# TC_TFT.net
KiCad netlist of a schematic drawn in EAGLE
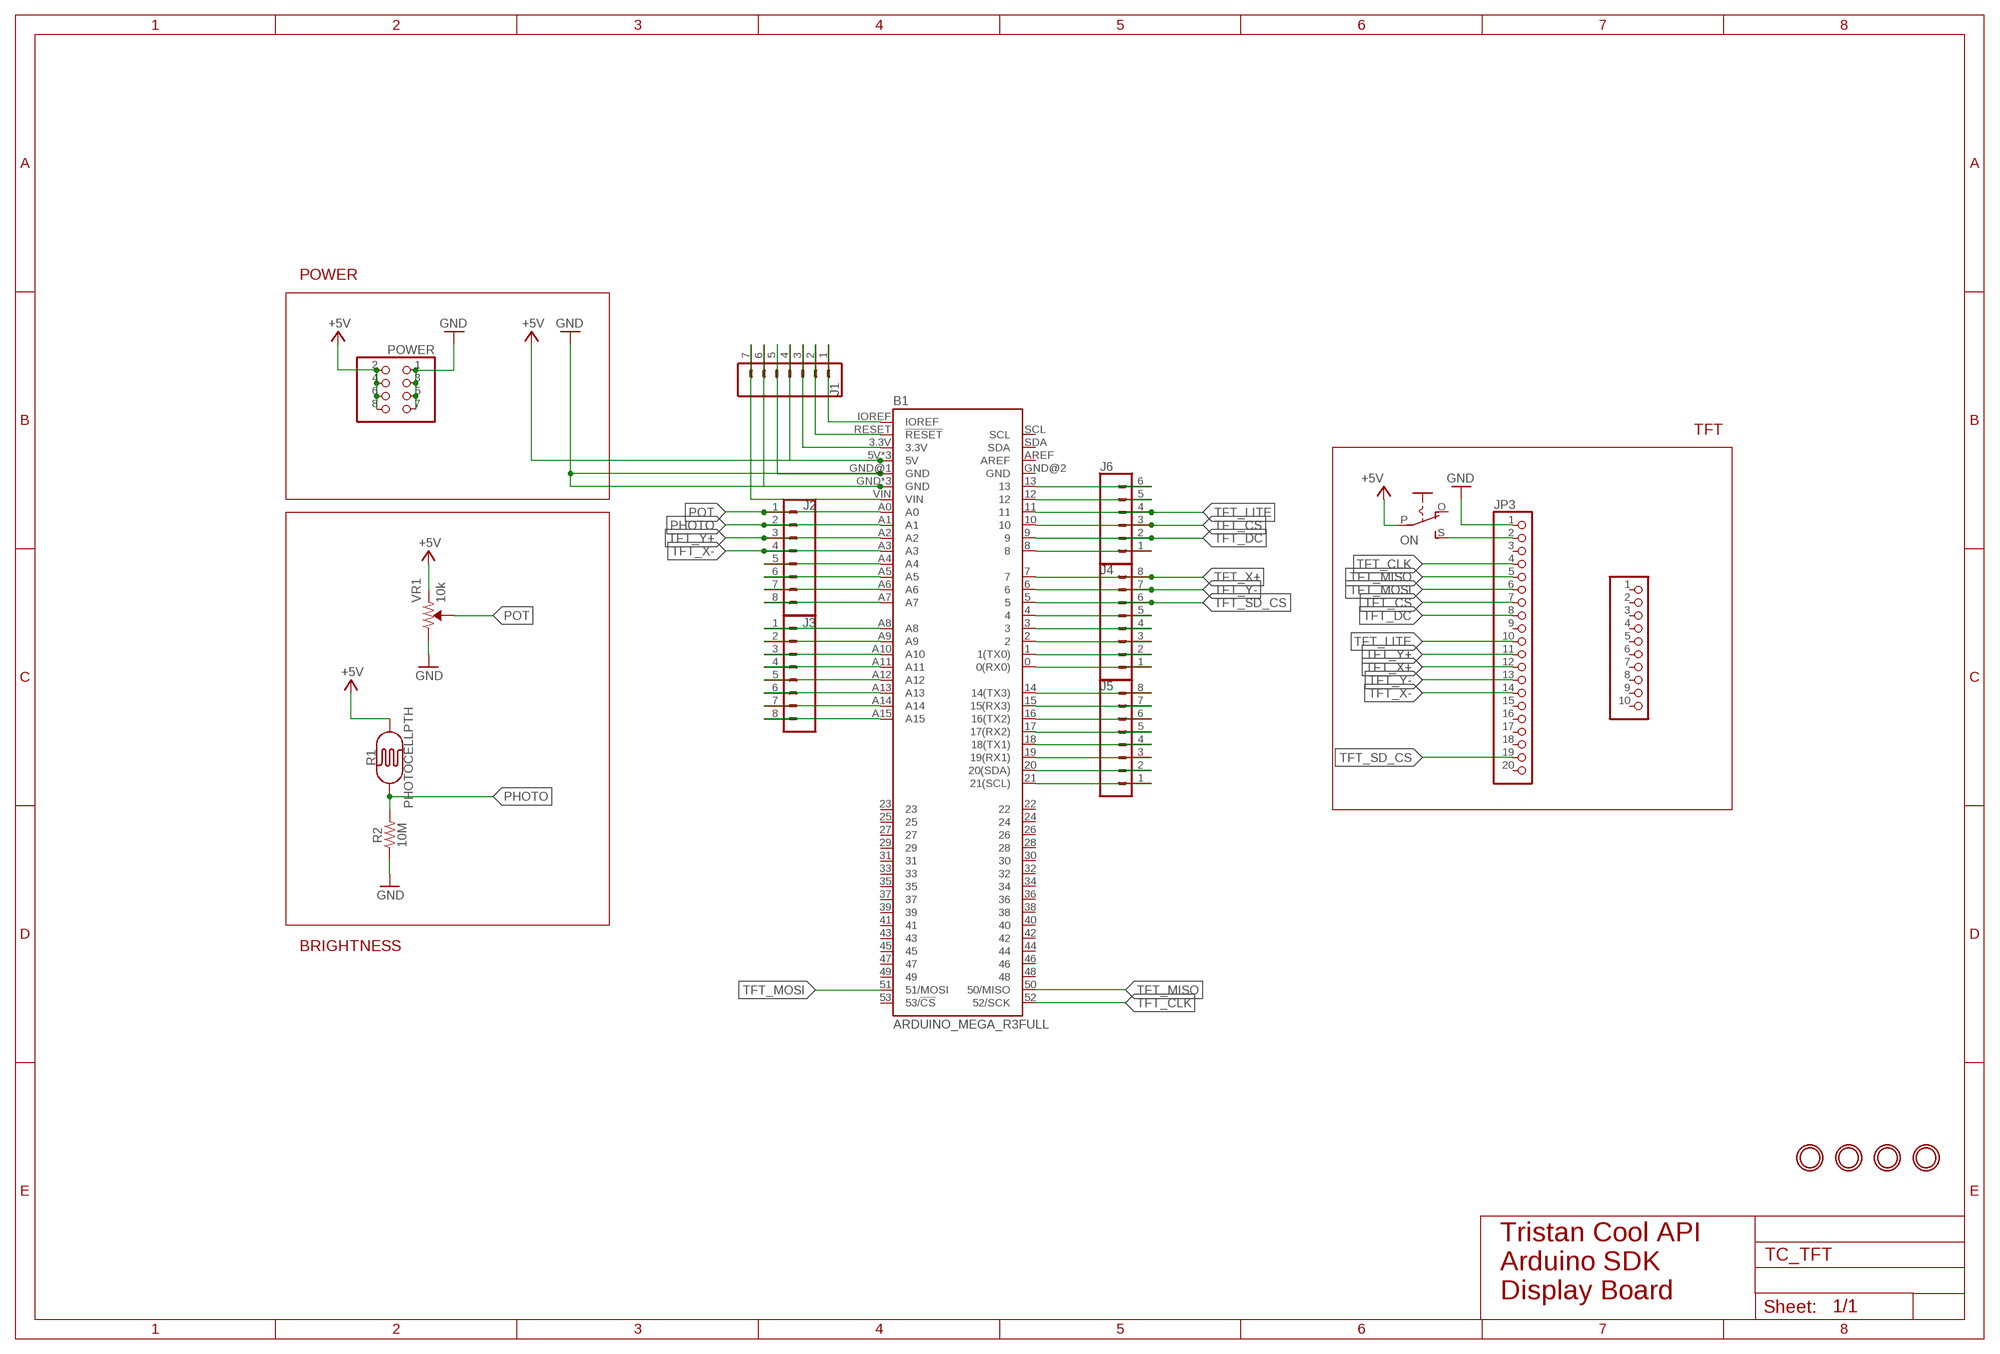
[diagram p0: schematic, sheet 1]

(export (version "E")
  (design (tool "Eeschema 10.0.6"))
  (components
    (comp (ref "B1")
      (value "ARDUINO_MEGA_R3FULL")
      (footprint "eagle-import:ARDUINO_MEGA_NO_SILK")
      (libsource (lib "eagle-import") (part "ARDUINO_MEGA_R3FULL"))
    )
    (comp (ref "J1")
      (value "CONN_07")
      (footprint "eagle-import:1X07")
      (libsource (lib "eagle-import") (part "CONN_07"))
    )
    (comp (ref "J2")
      (value "CONN_08\"")
      (footprint "eagle-import:1X08")
      (libsource (lib "eagle-import") (part "CONN_08{dblquote}"))
    )
    (comp (ref "J3")
      (value "CONN_08\"")
      (footprint "eagle-import:1X08")
      (libsource (lib "eagle-import") (part "CONN_08{dblquote}"))
    )
    (comp (ref "J4")
      (value "CONN_08\"")
      (footprint "eagle-import:1X08")
      (libsource (lib "eagle-import") (part "CONN_08{dblquote}"))
    )
    (comp (ref "J5")
      (value "CONN_08\"")
      (footprint "eagle-import:1X08")
      (libsource (lib "eagle-import") (part "CONN_08{dblquote}"))
    )
    (comp (ref "J6")
      (value "CONN_06SILK_FEMALE_PTH")
      (footprint "eagle-import:1X06")
      (libsource (lib "eagle-import") (part "CONN_06SILK_FEMALE_PTH"))
    )
    (comp (ref "JP3")
      (value "HEADER-1X20ROUND")
      (footprint "eagle-import:1X20_ROUND")
      (libsource (lib "eagle-import") (part "HEADER-1X20ROUND"))
    )
    (comp (ref "ON")
      (value "EG1218S")
      (footprint "eagle-import:EG1218")
      (libsource (lib "eagle-import") (part "EG1218S"))
    )
    (comp (ref "POWER")
      (value "PINHD-2X4")
      (footprint "eagle-import:2X04")
      (libsource (lib "eagle-import") (part "PINHD-2X4"))
    )
    (comp (ref "R1")
      (value "PHOTOCELLPTH")
      (footprint "eagle-import:PHOTOCELL")
      (libsource (lib "eagle-import") (part "PHOTOCELLPTH"))
    )
    (comp (ref "R2")
      (value "10M")
      (footprint "eagle-import:0603")
      (libsource (lib "eagle-import") (part "10MOHM-0603-1/10W-5%"))
    )
    (comp (ref "U$1")
      (value "MOUNTINGHOLE3.0THIN")
      (footprint "eagle-import:MOUNTINGHOLE_3.0_PLATEDTHIN")
      (libsource (lib "eagle-import") (part "MOUNTINGHOLE3.0THIN"))
    )
    (comp (ref "U$2")
      (value "MOUNTINGHOLE3.0THIN")
      (footprint "eagle-import:MOUNTINGHOLE_3.0_PLATEDTHIN")
      (libsource (lib "eagle-import") (part "MOUNTINGHOLE3.0THIN"))
    )
    (comp (ref "U$3")
      (value "MOUNTINGHOLE3.0THIN")
      (footprint "eagle-import:MOUNTINGHOLE_3.0_PLATEDTHIN")
      (libsource (lib "eagle-import") (part "MOUNTINGHOLE3.0THIN"))
    )
    (comp (ref "U$4")
      (value "MOUNTINGHOLE3.0THIN")
      (footprint "eagle-import:MOUNTINGHOLE_3.0_PLATEDTHIN")
      (libsource (lib "eagle-import") (part "MOUNTINGHOLE3.0THIN"))
    )
    (comp (ref "U$5")
      (value "PINHD-1X10")
      (footprint "eagle-import:1X10-BIG")
      (libsource (lib "eagle-import") (part "PINHD-1X10"))
    )
    (comp (ref "VR1")
      (value "10k")
      (footprint "eagle-import:TRIMPOT-PTH-3386U")
      (libsource (lib "eagle-import") (part "TRIMPOT-PTH-10MM-KNOB-1/2W-10%"))
    )
  )
  (nets
    (net (code "1") (name "+5V") (class "Default")
      (node (ref "B1") (pin "5V") (pinfunction "5V_5V") (pintype "bidirectional"))
      (node (ref "B1") (pin "5V@1") (pinfunction "5V_5V@1") (pintype "bidirectional"))
      (node (ref "B1") (pin "5V@2") (pinfunction "5V_5V@2") (pintype "bidirectional"))
      (node (ref "J1") (pin "4") (pinfunction "4_4") (pintype "passive"))
      (node (ref "ON") (pin "P") (pinfunction "P_P") (pintype "passive"))
      (node (ref "POWER") (pin "2") (pinfunction "2_2") (pintype "passive"))
      (node (ref "POWER") (pin "4") (pinfunction "4_4") (pintype "passive"))
      (node (ref "POWER") (pin "6") (pinfunction "6_6") (pintype "passive"))
      (node (ref "POWER") (pin "8") (pinfunction "8_8") (pintype "passive"))
      (node (ref "R1") (pin "2") (pinfunction "P$2_2") (pintype "bidirectional"))
      (node (ref "VR1") (pin "1") (pinfunction "CCW_1") (pintype "passive"))
    )
    (net (code "2") (name "GND") (class "Default")
      (node (ref "B1") (pin "GND") (pinfunction "GND_GND") (pintype "bidirectional"))
      (node (ref "B1") (pin "GND@1") (pinfunction "GND_GND@1") (pintype "bidirectional"))
      (node (ref "B1") (pin "GND@3") (pinfunction "GND_GND@3") (pintype "bidirectional"))
      (node (ref "B1") (pin "GND@4") (pinfunction "GND_GND@4") (pintype "bidirectional"))
      (node (ref "J1") (pin "5") (pinfunction "5_5") (pintype "passive"))
      (node (ref "J1") (pin "6") (pinfunction "6_6") (pintype "passive"))
      (node (ref "JP3") (pin "1") (pinfunction "1_1") (pintype "passive"))
      (node (ref "POWER") (pin "1") (pinfunction "1_1") (pintype "passive"))
      (node (ref "POWER") (pin "3") (pinfunction "3_3") (pintype "passive"))
      (node (ref "POWER") (pin "5") (pinfunction "5_5") (pintype "passive"))
      (node (ref "POWER") (pin "7") (pinfunction "7_7") (pintype "passive"))
      (node (ref "R2") (pin "1") (pinfunction "1_1") (pintype "passive"))
      (node (ref "VR1") (pin "3") (pinfunction "CW_3") (pintype "passive"))
    )
    (net (code "3") (name "Net-(B1-0(RX0))") (class "Default")
      (node (ref "B1") (pin "0") (pinfunction "0(RX0)_0") (pintype "bidirectional"))
      (node (ref "J4") (pin "1") (pinfunction "1_1") (pintype "passive"))
    )
    (net (code "4") (name "Net-(B1-1(TX0))") (class "Default")
      (node (ref "B1") (pin "1") (pinfunction "1(TX0)_1") (pintype "bidirectional"))
      (node (ref "J4") (pin "2") (pinfunction "2_2") (pintype "passive"))
    )
    (net (code "5") (name "Net-(B1-14(TX3))") (class "Default")
      (node (ref "B1") (pin "14") (pinfunction "14(TX3)_14") (pintype "bidirectional"))
      (node (ref "J5") (pin "8") (pinfunction "8_8") (pintype "passive"))
    )
    (net (code "6") (name "Net-(B1-15(RX3))") (class "Default")
      (node (ref "B1") (pin "15") (pinfunction "15(RX3)_15") (pintype "bidirectional"))
      (node (ref "J5") (pin "7") (pinfunction "7_7") (pintype "passive"))
    )
    (net (code "7") (name "Net-(B1-16(TX2))") (class "Default")
      (node (ref "B1") (pin "16") (pinfunction "16(TX2)_16") (pintype "bidirectional"))
      (node (ref "J5") (pin "6") (pinfunction "6_6") (pintype "passive"))
    )
    (net (code "8") (name "Net-(B1-17(RX2))") (class "Default")
      (node (ref "B1") (pin "17") (pinfunction "17(RX2)_17") (pintype "bidirectional"))
      (node (ref "J5") (pin "5") (pinfunction "5_5") (pintype "passive"))
    )
    (net (code "9") (name "Net-(B1-18(TX1))") (class "Default")
      (node (ref "B1") (pin "18") (pinfunction "18(TX1)_18") (pintype "bidirectional"))
      (node (ref "J5") (pin "4") (pinfunction "4_4") (pintype "passive"))
    )
    (net (code "10") (name "Net-(B1-19(RX1))") (class "Default")
      (node (ref "B1") (pin "19") (pinfunction "19(RX1)_19") (pintype "bidirectional"))
      (node (ref "J5") (pin "3") (pinfunction "3_3") (pintype "passive"))
    )
    (net (code "11") (name "Net-(B1-20(SDA))") (class "Default")
      (node (ref "B1") (pin "20") (pinfunction "20(SDA)_20") (pintype "bidirectional"))
      (node (ref "J5") (pin "2") (pinfunction "2_2") (pintype "passive"))
    )
    (net (code "12") (name "Net-(B1-21(SCL))") (class "Default")
      (node (ref "B1") (pin "21") (pinfunction "21(SCL)_21") (pintype "bidirectional"))
      (node (ref "J5") (pin "1") (pinfunction "1_1") (pintype "passive"))
    )
    (net (code "13") (name "Net-(B1-Pad2)") (class "Default")
      (node (ref "B1") (pin "2") (pinfunction "2_2") (pintype "bidirectional"))
      (node (ref "J4") (pin "3") (pinfunction "3_3") (pintype "passive"))
    )
    (net (code "14") (name "Net-(B1-Pad3)") (class "Default")
      (node (ref "B1") (pin "3") (pinfunction "3_3") (pintype "bidirectional"))
      (node (ref "J4") (pin "4") (pinfunction "4_4") (pintype "passive"))
    )
    (net (code "15") (name "Net-(B1-Pad3.3V)") (class "Default")
      (node (ref "B1") (pin "3.3V") (pinfunction "3.3V_3.3V") (pintype "bidirectional"))
      (node (ref "J1") (pin "3") (pinfunction "3_3") (pintype "passive"))
    )
    (net (code "16") (name "Net-(B1-Pad4)") (class "Default")
      (node (ref "B1") (pin "4") (pinfunction "4_4") (pintype "bidirectional"))
      (node (ref "J4") (pin "5") (pinfunction "5_5") (pintype "passive"))
    )
    (net (code "17") (name "Net-(B1-Pad8)") (class "Default")
      (node (ref "B1") (pin "8") (pinfunction "8_8") (pintype "bidirectional"))
      (node (ref "J6") (pin "1") (pinfunction "1_1") (pintype "passive"))
    )
    (net (code "18") (name "Net-(B1-Pad12)") (class "Default")
      (node (ref "B1") (pin "12") (pinfunction "12_12") (pintype "bidirectional"))
      (node (ref "J6") (pin "5") (pinfunction "5_5") (pintype "passive"))
    )
    (net (code "19") (name "Net-(B1-Pad13)") (class "Default")
      (node (ref "B1") (pin "13") (pinfunction "13_13") (pintype "bidirectional"))
      (node (ref "J6") (pin "6") (pinfunction "6_6") (pintype "passive"))
    )
    (net (code "20") (name "Net-(B1-PadA4)") (class "Default")
      (node (ref "B1") (pin "A4") (pinfunction "A4_A4") (pintype "bidirectional"))
      (node (ref "J2") (pin "5") (pinfunction "5_5") (pintype "passive"))
    )
    (net (code "21") (name "Net-(B1-PadA5)") (class "Default")
      (node (ref "B1") (pin "A5") (pinfunction "A5_A5") (pintype "bidirectional"))
      (node (ref "J2") (pin "6") (pinfunction "6_6") (pintype "passive"))
    )
    (net (code "22") (name "Net-(B1-PadA6)") (class "Default")
      (node (ref "B1") (pin "A6") (pinfunction "A6_A6") (pintype "bidirectional"))
      (node (ref "J2") (pin "7") (pinfunction "7_7") (pintype "passive"))
    )
    (net (code "23") (name "Net-(B1-PadA7)") (class "Default")
      (node (ref "B1") (pin "A7") (pinfunction "A7_A7") (pintype "bidirectional"))
      (node (ref "J2") (pin "8") (pinfunction "8_8") (pintype "passive"))
    )
    (net (code "24") (name "Net-(B1-PadA8)") (class "Default")
      (node (ref "B1") (pin "A8") (pinfunction "A8_A8") (pintype "bidirectional"))
      (node (ref "J3") (pin "1") (pinfunction "1_1") (pintype "passive"))
    )
    (net (code "25") (name "Net-(B1-PadA9)") (class "Default")
      (node (ref "B1") (pin "A9") (pinfunction "A9_A9") (pintype "bidirectional"))
      (node (ref "J3") (pin "2") (pinfunction "2_2") (pintype "passive"))
    )
    (net (code "26") (name "Net-(B1-PadA10)") (class "Default")
      (node (ref "B1") (pin "A10") (pinfunction "A10_A10") (pintype "bidirectional"))
      (node (ref "J3") (pin "3") (pinfunction "3_3") (pintype "passive"))
    )
    (net (code "27") (name "Net-(B1-PadA11)") (class "Default")
      (node (ref "B1") (pin "A11") (pinfunction "A11_A11") (pintype "bidirectional"))
      (node (ref "J3") (pin "4") (pinfunction "4_4") (pintype "passive"))
    )
    (net (code "28") (name "Net-(B1-PadA12)") (class "Default")
      (node (ref "B1") (pin "A12") (pinfunction "A12_A12") (pintype "bidirectional"))
      (node (ref "J3") (pin "5") (pinfunction "5_5") (pintype "passive"))
    )
    (net (code "29") (name "Net-(B1-PadA13)") (class "Default")
      (node (ref "B1") (pin "A13") (pinfunction "A13_A13") (pintype "bidirectional"))
      (node (ref "J3") (pin "6") (pinfunction "6_6") (pintype "passive"))
    )
    (net (code "30") (name "Net-(B1-PadA14)") (class "Default")
      (node (ref "B1") (pin "A14") (pinfunction "A14_A14") (pintype "bidirectional"))
      (node (ref "J3") (pin "7") (pinfunction "7_7") (pintype "passive"))
    )
    (net (code "31") (name "Net-(B1-PadA15)") (class "Default")
      (node (ref "B1") (pin "A15") (pinfunction "A15_A15") (pintype "bidirectional"))
      (node (ref "J3") (pin "8") (pinfunction "8_8") (pintype "passive"))
    )
    (net (code "32") (name "Net-(B1-PadIOREF)") (class "Default")
      (node (ref "B1") (pin "IOREF") (pinfunction "IOREF_IOREF") (pintype "bidirectional"))
      (node (ref "J1") (pin "1") (pinfunction "1_1") (pintype "passive"))
    )
    (net (code "33") (name "Net-(B1-PadVIN)") (class "Default")
      (node (ref "B1") (pin "VIN") (pinfunction "VIN_VIN") (pintype "bidirectional"))
      (node (ref "J1") (pin "7") (pinfunction "7_7") (pintype "passive"))
    )
    (net (code "34") (name "Net-(B1-~{RESET})") (class "Default")
      (node (ref "B1") (pin "RESET") (pinfunction "~{RESET}_RESET") (pintype "bidirectional"))
      (node (ref "J1") (pin "2") (pinfunction "2_2") (pintype "passive"))
    )
    (net (code "35") (name "Net-(JP3-Pad2)") (class "Default")
      (node (ref "JP3") (pin "2") (pinfunction "2_2") (pintype "passive"))
      (node (ref "ON") (pin "S") (pinfunction "S_S") (pintype "passive"))
    )
    (net (code "36") (name "PHOTO") (class "Default")
      (node (ref "B1") (pin "A1") (pinfunction "A1_A1") (pintype "bidirectional"))
      (node (ref "J2") (pin "2") (pinfunction "2_2") (pintype "passive"))
      (node (ref "R1") (pin "1") (pinfunction "P$1_1") (pintype "bidirectional"))
      (node (ref "R2") (pin "2") (pinfunction "2_2") (pintype "passive"))
    )
    (net (code "37") (name "POT") (class "Default")
      (node (ref "B1") (pin "A0") (pinfunction "A0_A0") (pintype "bidirectional"))
      (node (ref "J2") (pin "1") (pinfunction "1_1") (pintype "passive"))
      (node (ref "VR1") (pin "2") (pinfunction "WIPER_2") (pintype "passive"))
    )
    (net (code "38") (name "TFT_CLK") (class "Default")
      (node (ref "B1") (pin "52") (pinfunction "52/SCK_52") (pintype "bidirectional"))
      (node (ref "JP3") (pin "4") (pinfunction "4_4") (pintype "passive"))
    )
    (net (code "39") (name "TFT_CS") (class "Default")
      (node (ref "B1") (pin "10") (pinfunction "10_10") (pintype "bidirectional"))
      (node (ref "J6") (pin "3") (pinfunction "3_3") (pintype "passive"))
      (node (ref "JP3") (pin "7") (pinfunction "7_7") (pintype "passive"))
    )
    (net (code "40") (name "TFT_DC") (class "Default")
      (node (ref "B1") (pin "9") (pinfunction "9_9") (pintype "bidirectional"))
      (node (ref "J6") (pin "2") (pinfunction "2_2") (pintype "passive"))
      (node (ref "JP3") (pin "8") (pinfunction "8_8") (pintype "passive"))
    )
    (net (code "41") (name "TFT_LITE") (class "Default")
      (node (ref "B1") (pin "11") (pinfunction "11_11") (pintype "bidirectional"))
      (node (ref "J6") (pin "4") (pinfunction "4_4") (pintype "passive"))
      (node (ref "JP3") (pin "10") (pinfunction "10_10") (pintype "passive"))
    )
    (net (code "42") (name "TFT_MISO") (class "Default")
      (node (ref "B1") (pin "50") (pinfunction "50/MISO_50") (pintype "bidirectional"))
      (node (ref "JP3") (pin "5") (pinfunction "5_5") (pintype "passive"))
    )
    (net (code "43") (name "TFT_MOSI") (class "Default")
      (node (ref "B1") (pin "51") (pinfunction "51/MOSI_51") (pintype "bidirectional"))
      (node (ref "JP3") (pin "6") (pinfunction "6_6") (pintype "passive"))
    )
    (net (code "44") (name "TFT_SD_CS") (class "Default")
      (node (ref "B1") (pin "5") (pinfunction "5_5") (pintype "bidirectional"))
      (node (ref "J4") (pin "6") (pinfunction "6_6") (pintype "passive"))
      (node (ref "JP3") (pin "19") (pinfunction "19_19") (pintype "passive"))
    )
    (net (code "45") (name "TFT_X+") (class "Default")
      (node (ref "B1") (pin "7") (pinfunction "7_7") (pintype "bidirectional"))
      (node (ref "J4") (pin "8") (pinfunction "8_8") (pintype "passive"))
      (node (ref "JP3") (pin "12") (pinfunction "12_12") (pintype "passive"))
    )
    (net (code "46") (name "TFT_X-") (class "Default")
      (node (ref "B1") (pin "A3") (pinfunction "A3_A3") (pintype "bidirectional"))
      (node (ref "J2") (pin "4") (pinfunction "4_4") (pintype "passive"))
      (node (ref "JP3") (pin "14") (pinfunction "14_14") (pintype "passive"))
    )
    (net (code "47") (name "TFT_Y+") (class "Default")
      (node (ref "B1") (pin "A2") (pinfunction "A2_A2") (pintype "bidirectional"))
      (node (ref "J2") (pin "3") (pinfunction "3_3") (pintype "passive"))
      (node (ref "JP3") (pin "11") (pinfunction "11_11") (pintype "passive"))
    )
    (net (code "48") (name "TFT_Y-") (class "Default")
      (node (ref "B1") (pin "6") (pinfunction "6_6") (pintype "bidirectional"))
      (node (ref "J4") (pin "7") (pinfunction "7_7") (pintype "passive"))
      (node (ref "JP3") (pin "13") (pinfunction "13_13") (pintype "passive"))
    )
    (net (code "49") (name "unconnected-(B1-53{slash}~{CS}-Pad53)") (class "Default")
      (node (ref "B1") (pin "53") (pinfunction "53/~{CS}_53") (pintype "bidirectional"))
    )
    (net (code "50") (name "unconnected-(B1-GND-PadGND@2)") (class "Default")
      (node (ref "B1") (pin "GND@2") (pinfunction "GND_GND@2") (pintype "bidirectional"))
    )
    (net (code "51") (name "unconnected-(B1-Pad22)") (class "Default")
      (node (ref "B1") (pin "22") (pinfunction "22_22") (pintype "bidirectional"))
    )
    (net (code "52") (name "unconnected-(B1-Pad23)") (class "Default")
      (node (ref "B1") (pin "23") (pinfunction "23_23") (pintype "bidirectional"))
    )
    (net (code "53") (name "unconnected-(B1-Pad24)") (class "Default")
      (node (ref "B1") (pin "24") (pinfunction "24_24") (pintype "bidirectional"))
    )
    (net (code "54") (name "unconnected-(B1-Pad25)") (class "Default")
      (node (ref "B1") (pin "25") (pinfunction "25_25") (pintype "bidirectional"))
    )
    (net (code "55") (name "unconnected-(B1-Pad26)") (class "Default")
      (node (ref "B1") (pin "26") (pinfunction "26_26") (pintype "bidirectional"))
    )
    (net (code "56") (name "unconnected-(B1-Pad27)") (class "Default")
      (node (ref "B1") (pin "27") (pinfunction "27_27") (pintype "bidirectional"))
    )
    (net (code "57") (name "unconnected-(B1-Pad28)") (class "Default")
      (node (ref "B1") (pin "28") (pinfunction "28_28") (pintype "bidirectional"))
    )
    (net (code "58") (name "unconnected-(B1-Pad29)") (class "Default")
      (node (ref "B1") (pin "29") (pinfunction "29_29") (pintype "bidirectional"))
    )
    (net (code "59") (name "unconnected-(B1-Pad30)") (class "Default")
      (node (ref "B1") (pin "30") (pinfunction "30_30") (pintype "bidirectional"))
    )
    (net (code "60") (name "unconnected-(B1-Pad31)") (class "Default")
      (node (ref "B1") (pin "31") (pinfunction "31_31") (pintype "bidirectional"))
    )
    (net (code "61") (name "unconnected-(B1-Pad32)") (class "Default")
      (node (ref "B1") (pin "32") (pinfunction "32_32") (pintype "bidirectional"))
    )
    (net (code "62") (name "unconnected-(B1-Pad33)") (class "Default")
      (node (ref "B1") (pin "33") (pinfunction "33_33") (pintype "bidirectional"))
    )
    (net (code "63") (name "unconnected-(B1-Pad34)") (class "Default")
      (node (ref "B1") (pin "34") (pinfunction "34_34") (pintype "bidirectional"))
    )
    (net (code "64") (name "unconnected-(B1-Pad35)") (class "Default")
      (node (ref "B1") (pin "35") (pinfunction "35_35") (pintype "bidirectional"))
    )
    (net (code "65") (name "unconnected-(B1-Pad36)") (class "Default")
      (node (ref "B1") (pin "36") (pinfunction "36_36") (pintype "bidirectional"))
    )
    (net (code "66") (name "unconnected-(B1-Pad37)") (class "Default")
      (node (ref "B1") (pin "37") (pinfunction "37_37") (pintype "bidirectional"))
    )
    (net (code "67") (name "unconnected-(B1-Pad38)") (class "Default")
      (node (ref "B1") (pin "38") (pinfunction "38_38") (pintype "bidirectional"))
    )
    (net (code "68") (name "unconnected-(B1-Pad39)") (class "Default")
      (node (ref "B1") (pin "39") (pinfunction "39_39") (pintype "bidirectional"))
    )
    (net (code "69") (name "unconnected-(B1-Pad40)") (class "Default")
      (node (ref "B1") (pin "40") (pinfunction "40_40") (pintype "bidirectional"))
    )
    (net (code "70") (name "unconnected-(B1-Pad41)") (class "Default")
      (node (ref "B1") (pin "41") (pinfunction "41_41") (pintype "bidirectional"))
    )
    (net (code "71") (name "unconnected-(B1-Pad42)") (class "Default")
      (node (ref "B1") (pin "42") (pinfunction "42_42") (pintype "bidirectional"))
    )
    (net (code "72") (name "unconnected-(B1-Pad43)") (class "Default")
      (node (ref "B1") (pin "43") (pinfunction "43_43") (pintype "bidirectional"))
    )
    (net (code "73") (name "unconnected-(B1-Pad44)") (class "Default")
      (node (ref "B1") (pin "44") (pinfunction "44_44") (pintype "bidirectional"))
    )
    (net (code "74") (name "unconnected-(B1-Pad45)") (class "Default")
      (node (ref "B1") (pin "45") (pinfunction "45_45") (pintype "bidirectional"))
    )
    (net (code "75") (name "unconnected-(B1-Pad46)") (class "Default")
      (node (ref "B1") (pin "46") (pinfunction "46_46") (pintype "bidirectional"))
    )
    (net (code "76") (name "unconnected-(B1-Pad47)") (class "Default")
      (node (ref "B1") (pin "47") (pinfunction "47_47") (pintype "bidirectional"))
    )
    (net (code "77") (name "unconnected-(B1-Pad48)") (class "Default")
      (node (ref "B1") (pin "48") (pinfunction "48_48") (pintype "bidirectional"))
    )
    (net (code "78") (name "unconnected-(B1-Pad49)") (class "Default")
      (node (ref "B1") (pin "49") (pinfunction "49_49") (pintype "bidirectional"))
    )
    (net (code "79") (name "unconnected-(B1-PadAREF)") (class "Default")
      (node (ref "B1") (pin "AREF") (pinfunction "AREF_AREF") (pintype "bidirectional"))
    )
    (net (code "80") (name "unconnected-(B1-PadSCL)") (class "Default")
      (node (ref "B1") (pin "SCL") (pinfunction "SCL_SCL") (pintype "bidirectional"))
    )
    (net (code "81") (name "unconnected-(B1-PadSDA)") (class "Default")
      (node (ref "B1") (pin "SDA") (pinfunction "SDA_SDA") (pintype "bidirectional"))
    )
    (net (code "82") (name "unconnected-(JP3-Pad3)") (class "Default")
      (node (ref "JP3") (pin "3") (pinfunction "3_3") (pintype "passive"))
    )
    (net (code "83") (name "unconnected-(JP3-Pad9)") (class "Default")
      (node (ref "JP3") (pin "9") (pinfunction "9_9") (pintype "passive"))
    )
    (net (code "84") (name "unconnected-(JP3-Pad15)") (class "Default")
      (node (ref "JP3") (pin "15") (pinfunction "15_15") (pintype "passive"))
    )
    (net (code "85") (name "unconnected-(JP3-Pad16)") (class "Default")
      (node (ref "JP3") (pin "16") (pinfunction "16_16") (pintype "passive"))
    )
    (net (code "86") (name "unconnected-(JP3-Pad17)") (class "Default")
      (node (ref "JP3") (pin "17") (pinfunction "17_17") (pintype "passive"))
    )
    (net (code "87") (name "unconnected-(JP3-Pad18)") (class "Default")
      (node (ref "JP3") (pin "18") (pinfunction "18_18") (pintype "passive"))
    )
    (net (code "88") (name "unconnected-(JP3-Pad20)") (class "Default")
      (node (ref "JP3") (pin "20") (pinfunction "20_20") (pintype "passive"))
    )
    (net (code "89") (name "unconnected-(ON-PadO)") (class "Default")
      (node (ref "ON") (pin "O") (pinfunction "O_O") (pintype "passive"))
    )
    (net (code "90") (name "unconnected-(U$5-Pad1)") (class "Default")
      (node (ref "U$5") (pin "1") (pinfunction "1_1") (pintype "passive"))
    )
    (net (code "91") (name "unconnected-(U$5-Pad2)") (class "Default")
      (node (ref "U$5") (pin "2") (pinfunction "2_2") (pintype "passive"))
    )
    (net (code "92") (name "unconnected-(U$5-Pad3)") (class "Default")
      (node (ref "U$5") (pin "3") (pinfunction "3_3") (pintype "passive"))
    )
    (net (code "93") (name "unconnected-(U$5-Pad4)") (class "Default")
      (node (ref "U$5") (pin "4") (pinfunction "4_4") (pintype "passive"))
    )
    (net (code "94") (name "unconnected-(U$5-Pad5)") (class "Default")
      (node (ref "U$5") (pin "5") (pinfunction "5_5") (pintype "passive"))
    )
    (net (code "95") (name "unconnected-(U$5-Pad6)") (class "Default")
      (node (ref "U$5") (pin "6") (pinfunction "6_6") (pintype "passive"))
    )
    (net (code "96") (name "unconnected-(U$5-Pad7)") (class "Default")
      (node (ref "U$5") (pin "7") (pinfunction "7_7") (pintype "passive"))
    )
    (net (code "97") (name "unconnected-(U$5-Pad8)") (class "Default")
      (node (ref "U$5") (pin "8") (pinfunction "8_8") (pintype "passive"))
    )
    (net (code "98") (name "unconnected-(U$5-Pad9)") (class "Default")
      (node (ref "U$5") (pin "9") (pinfunction "9_9") (pintype "passive"))
    )
    (net (code "99") (name "unconnected-(U$5-Pad10)") (class "Default")
      (node (ref "U$5") (pin "10") (pinfunction "10_10") (pintype "passive"))
    )
  )
)
